# Zhonji_ai8051__Board1_Schematic1__1_P1.net
KiCad netlist of a schematic drawn in Altium Designer
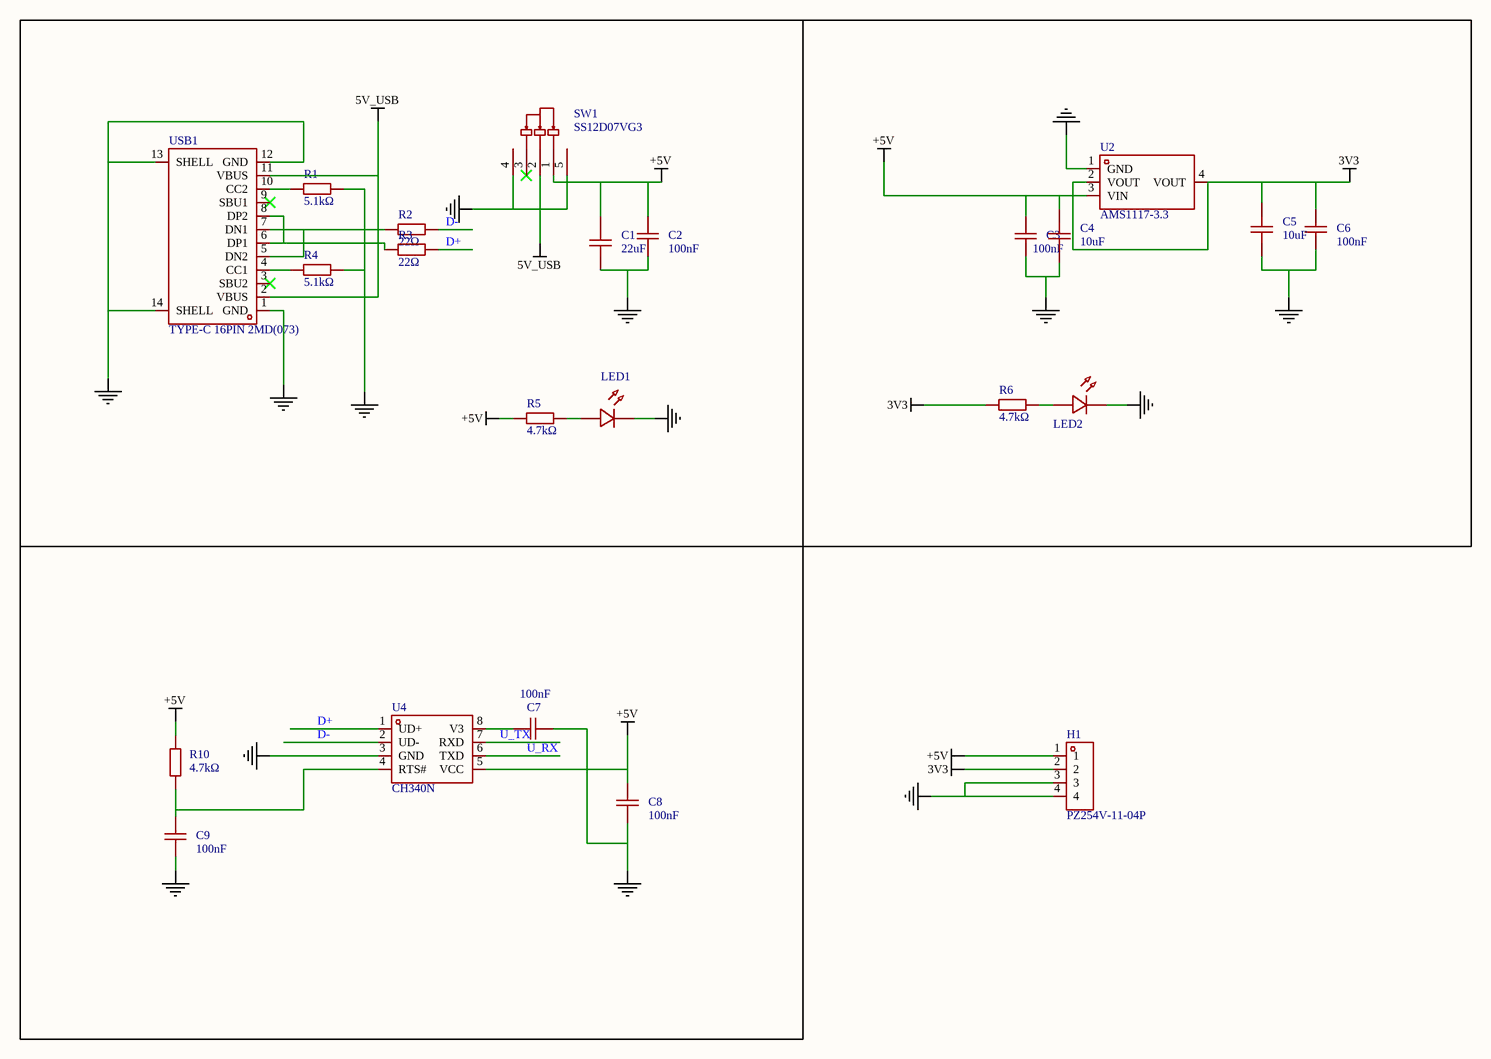
[diagram p0: Zhonji_ai8051__Board1_Schematic1__1_P1.schdoc]

(export (version "E")
  (design (tool "Eeschema 10.0.6"))
  (components
    (comp (ref "C1")
      (value "22uF")
      (footprint "C0603")
      (description "容值:22uF;精度:±20%;额定电压:16V;材质(温度系数):X5R;")
      (fields
        (field (name "MANUFACTURER") "HRE(芯声)")
        (field (name "MANUFACTURER PART") "CGA0603X5R226M160JT")
      )
      (libsource (lib "altium-import") (part "root_1_CGA0603X5R226M160JT_"))
    )
    (comp (ref "C2")
      (value "100nF")
      (footprint "C0603")
      (description "容值:100nF;精度:±10%;额定电压:50V;材质(温度系数):2X1;")
      (fields
        (field (name "MANUFACTURER") "TORCH(火炬)")
        (field (name "MANUFACTURER PART") "CT41G-0603-2X1-50V-0.1μF-K(N)")
      )
      (libsource (lib "altium-import") (part "root_1_CT41G-0603-2X1-50V-0.1μF-K(N)_"))
    )
    (comp (ref "C3")
      (value "100nF")
      (footprint "C0603")
      (description "容值:100nF;精度:±10%;额定电压:50V;材质(温度系数):2X1;")
      (fields
        (field (name "MANUFACTURER") "TORCH(火炬)")
        (field (name "MANUFACTURER PART") "CT41G-0603-2X1-50V-0.1μF-K(N)")
      )
      (libsource (lib "altium-import") (part "root_1_CT41G-0603-2X1-50V-0.1μF-K(N)_"))
    )
    (comp (ref "C4")
      (value "10uF")
      (footprint "C0603")
      (description "容值:10uF;精度:±20%;额定电压:25V;材质(温度系数):X5R;")
      (fields
        (field (name "MANUFACTURER") "SAMSUNG(三星)")
        (field (name "MANUFACTURER PART") "CL10A106MA8NRNC")
      )
      (libsource (lib "altium-import") (part "root_1_CL10A106MA8NRNC_"))
    )
    (comp (ref "C5")
      (value "10uF")
      (footprint "C0603")
      (description "容值:10uF;精度:±20%;额定电压:25V;材质(温度系数):X5R;")
      (fields
        (field (name "MANUFACTURER") "SAMSUNG(三星)")
        (field (name "MANUFACTURER PART") "CL10A106MA8NRNC")
      )
      (libsource (lib "altium-import") (part "root_1_CL10A106MA8NRNC_"))
    )
    (comp (ref "C6")
      (value "100nF")
      (footprint "C0603")
      (description "容值:100nF;精度:±10%;额定电压:50V;材质(温度系数):2X1;")
      (fields
        (field (name "MANUFACTURER") "TORCH(火炬)")
        (field (name "MANUFACTURER PART") "CT41G-0603-2X1-50V-0.1μF-K(N)")
      )
      (libsource (lib "altium-import") (part "root_1_CT41G-0603-2X1-50V-0.1μF-K(N)_"))
    )
    (comp (ref "C7")
      (value "100nF")
      (footprint "C0603")
      (description "容值:100nF;精度:±10%;额定电压:50V;材质(温度系数):2X1;")
      (fields
        (field (name "MANUFACTURER") "TORCH(火炬)")
        (field (name "MANUFACTURER PART") "CT41G-0603-2X1-50V-0.1μF-K(N)")
      )
      (libsource (lib "altium-import") (part "root_2_CT41G-0603-2X1-50V-0.1μF-K(N)_"))
    )
    (comp (ref "C8")
      (value "100nF")
      (footprint "C0603")
      (description "容值:100nF;精度:±10%;额定电压:50V;材质(温度系数):2X1;")
      (fields
        (field (name "MANUFACTURER") "TORCH(火炬)")
        (field (name "MANUFACTURER PART") "CT41G-0603-2X1-50V-0.1μF-K(N)")
      )
      (libsource (lib "altium-import") (part "root_1_CT41G-0603-2X1-50V-0.1μF-K(N)_"))
    )
    (comp (ref "C9")
      (value "100nF")
      (footprint "C0603")
      (description "容值:100nF;精度:±10%;额定电压:50V;材质(温度系数):2X1;")
      (fields
        (field (name "MANUFACTURER") "TORCH(火炬)")
        (field (name "MANUFACTURER PART") "CT41G-0603-2X1-50V-0.1μF-K(N)")
      )
      (libsource (lib "altium-import") (part "root_1_CT41G-0603-2X1-50V-0.1μF-K(N)_"))
    )
    (comp (ref "H1")
      (value "PZ254V-11-04P")
      (footprint "HDR-TH_4P-P2.54-V-M")
      (fields (field (name "MANUFACTURER") "XFCN(兴飞)"))
      (libsource (lib "altium-import") (part "root_0_PZ254V-11-04P_"))
    )
    (comp (ref "LED1")
      (value "LED_0603-G")
      (footprint "LED_0603")
      (libsource (lib "altium-import") (part "root_0_LED_0603-G_"))
    )
    (comp (ref "LED2")
      (value "LED_0603-R")
      (footprint "LED_0603")
      (libsource (lib "altium-import") (part "root_0_LED_0603-R_"))
    )
    (comp (ref "R1")
      (value "5.1kΩ")
      (footprint "R0603")
      (description "电阻类型:厚膜电阻;阻值:5.1kΩ;精度:±1%;功率:100mW;最大工作电压:75V;温度系数:±100ppm/℃;")
      (fields
        (field (name "MANUFACTURER") "UNI-ROYAL(厚声)")
        (field (name "MANUFACTURER PART") "0603WAF5101T5E")
      )
      (libsource (lib "altium-import") (part "root_0_0603WAF5101T5E_"))
    )
    (comp (ref "R2")
      (value "22Ω")
      (footprint "R0603")
      (description "电阻类型:厚膜电阻;阻值:22Ω;精度:±1%;功率:100mW;最大工作电压:75V;温度系数:±100ppm/℃;")
      (fields
        (field (name "MANUFACTURER") "UNI-ROYAL(厚声)")
        (field (name "MANUFACTURER PART") "0603WAF220JT5E")
      )
      (libsource (lib "altium-import") (part "root_0_0603WAF220JT5E_"))
    )
    (comp (ref "R3")
      (value "22Ω")
      (footprint "R0603")
      (description "电阻类型:厚膜电阻;阻值:22Ω;精度:±1%;功率:100mW;最大工作电压:75V;温度系数:±100ppm/℃;")
      (fields
        (field (name "MANUFACTURER") "UNI-ROYAL(厚声)")
        (field (name "MANUFACTURER PART") "0603WAF220JT5E")
      )
      (libsource (lib "altium-import") (part "root_0_0603WAF220JT5E_"))
    )
    (comp (ref "R4")
      (value "5.1kΩ")
      (footprint "R0603")
      (description "电阻类型:厚膜电阻;阻值:5.1kΩ;精度:±1%;功率:100mW;最大工作电压:75V;温度系数:±100ppm/℃;")
      (fields
        (field (name "MANUFACTURER") "UNI-ROYAL(厚声)")
        (field (name "MANUFACTURER PART") "0603WAF5101T5E")
      )
      (libsource (lib "altium-import") (part "root_0_0603WAF5101T5E_"))
    )
    (comp (ref "R5")
      (value "4.7kΩ")
      (footprint "R0603")
      (description "电阻类型:厚膜电阻;阻值:4.7kΩ;精度:±1%;功率:100mW;最大工作电压:75V;温度系数:±100ppm/℃;")
      (fields
        (field (name "MANUFACTURER") "UNI-ROYAL(厚声)")
        (field (name "MANUFACTURER PART") "0603WAF4701T5E")
      )
      (libsource (lib "altium-import") (part "root_0_0603WAF4701T5E_"))
    )
    (comp (ref "R6")
      (value "4.7kΩ")
      (footprint "R0603")
      (description "电阻类型:厚膜电阻;阻值:4.7kΩ;精度:±1%;功率:100mW;最大工作电压:75V;温度系数:±100ppm/℃;")
      (fields
        (field (name "MANUFACTURER") "UNI-ROYAL(厚声)")
        (field (name "MANUFACTURER PART") "0603WAF4701T5E")
      )
      (libsource (lib "altium-import") (part "root_0_0603WAF4701T5E_"))
    )
    (comp (ref "R10")
      (value "4.7kΩ")
      (footprint "R0603")
      (description "电阻类型:厚膜电阻;阻值:4.7kΩ;精度:±1%;功率:100mW;最大工作电压:75V;温度系数:±100ppm/℃;")
      (fields
        (field (name "MANUFACTURER") "UNI-ROYAL(厚声)")
        (field (name "MANUFACTURER PART") "0603WAF4701T5E")
      )
      (libsource (lib "altium-import") (part "root_1_0603WAF4701T5E_"))
    )
    (comp (ref "SW1")
      (value "SS12D07VG3")
      (footprint "SW-TH_SS12D07VG3")
      (description "电路结构:单刀双掷;安装方式:直插;开关颜色:-;额定电流(DC):500mA;额定电压(DC):50V;额定电流(AC):-;额定电压(AC):-;机械寿命:5千次;")
      (fields (field (name "MANUFACTURER") "SHOU HAN(首韩)"))
      (libsource (lib "altium-import") (part "root_2_SS12D07VG3_"))
    )
    (comp (ref "U2")
      (value "AMS1117-3.3")
      (footprint "SOT-223-3_L6.5-W3.4-P2.30-LS7.0-BR")
      (description "输出类型:固定;最大输入电压:-;输出电压:3.3V;最大输出电流:1A;电源纹波抑制比(PSRR):72dB@(120Hz);输出极性:正极;")
      (fields (field (name "MANUFACTURER") "AMS"))
      (libsource (lib "altium-import") (part "root_0_AMS1117-3.3_C6186_"))
    )
    (comp (ref "U4")
      (value "CH340N")
      (footprint "SOP-8_L4.9-W3.9-P1.27-LS6.0-BL")
      (fields (field (name "MANUFACTURER") "WCH(南京沁恒)"))
      (libsource (lib "altium-import") (part "root_0_CH340N_"))
    )
    (comp (ref "USB1")
      (value "TYPE-C 16PIN 2MD(073)")
      (footprint "USB-C-SMD_TYPE-C-6PIN-2MD-073")
      (description "连接器类型:Type-C;标准:USB 3.1;公母:母;安装方式:卧贴;触点数量:16P;端口数量:1;额定电流 - 电源:5A;工作温度范围:-25℃~+85℃;")
      (fields (field (name "MANUFACTURER") "SHOU HAN(首韩)"))
      (libsource (lib "altium-import") (part "root_2_TYPE-C 16PIN 2MD(073)_"))
    )
  )
  (nets
    (net (code "1") (name "+5V") (class "Default")
      (node (ref "C1") (pin "2") (pinfunction "2_2") (pintype "passive"))
      (node (ref "C2") (pin "2") (pinfunction "2_2") (pintype "passive"))
      (node (ref "C3") (pin "2") (pinfunction "2_2") (pintype "passive"))
      (node (ref "C4") (pin "2") (pinfunction "2_2") (pintype "passive"))
      (node (ref "C8") (pin "2") (pinfunction "2_2") (pintype "passive"))
      (node (ref "H1") (pin "1") (pinfunction "1_1") (pintype "passive"))
      (node (ref "R10") (pin "2") (pinfunction "2_2") (pintype "passive"))
      (node (ref "R5") (pin "1") (pinfunction "1_1") (pintype "passive"))
      (node (ref "SW1") (pin "1") (pinfunction "1_1") (pintype "passive"))
      (node (ref "U2") (pin "3") (pinfunction "VIN_3") (pintype "passive"))
      (node (ref "U4") (pin "5") (pinfunction "VCC_5") (pintype "passive"))
    )
    (net (code "2") (name "/D+") (class "Default")
      (node (ref "R3") (pin "2") (pinfunction "2_2") (pintype "passive"))
      (node (ref "U4") (pin "1") (pinfunction "UD+_1") (pintype "passive"))
    )
    (net (code "3") (name "/D-") (class "Default")
      (node (ref "R2") (pin "2") (pinfunction "2_2") (pintype "passive"))
      (node (ref "U4") (pin "2") (pinfunction "UD-_2") (pintype "passive"))
    )
    (net (code "4") (name "/U_RX") (class "Default")
      (node (ref "U4") (pin "6") (pinfunction "TXD_6") (pintype "passive"))
    )
    (net (code "5") (name "/U_TX") (class "Default")
      (node (ref "U4") (pin "7") (pinfunction "RXD_7") (pintype "passive"))
    )
    (net (code "6") (name "3V3") (class "Default")
      (node (ref "C5") (pin "2") (pinfunction "2_2") (pintype "passive"))
      (node (ref "C6") (pin "2") (pinfunction "2_2") (pintype "passive"))
      (node (ref "H1") (pin "2") (pinfunction "2_2") (pintype "passive"))
      (node (ref "R6") (pin "1") (pinfunction "1_1") (pintype "passive"))
      (node (ref "U2") (pin "2") (pinfunction "VOUT_2") (pintype "passive"))
      (node (ref "U2") (pin "4") (pinfunction "VOUT_4") (pintype "passive"))
    )
    (net (code "7") (name "5V_USB") (class "Default")
      (node (ref "SW1") (pin "2") (pinfunction "2_2") (pintype "passive"))
      (node (ref "USB1") (pin "11") (pinfunction "VBUS_11") (pintype "passive"))
      (node (ref "USB1") (pin "2") (pinfunction "VBUS_2") (pintype "passive"))
    )
    (net (code "8") (name "GND") (class "Default")
      (node (ref "C1") (pin "1") (pinfunction "1_1") (pintype "passive"))
      (node (ref "C2") (pin "1") (pinfunction "1_1") (pintype "passive"))
      (node (ref "C3") (pin "1") (pinfunction "1_1") (pintype "passive"))
      (node (ref "C4") (pin "1") (pinfunction "1_1") (pintype "passive"))
      (node (ref "C5") (pin "1") (pinfunction "1_1") (pintype "passive"))
      (node (ref "C6") (pin "1") (pinfunction "1_1") (pintype "passive"))
      (node (ref "C7") (pin "1") (pinfunction "1_1") (pintype "passive"))
      (node (ref "C8") (pin "1") (pinfunction "1_1") (pintype "passive"))
      (node (ref "C9") (pin "1") (pinfunction "1_1") (pintype "passive"))
      (node (ref "H1") (pin "3") (pinfunction "3_3") (pintype "passive"))
      (node (ref "H1") (pin "4") (pinfunction "4_4") (pintype "passive"))
      (node (ref "LED1") (pin "1") (pinfunction "C_1") (pintype "passive"))
      (node (ref "LED2") (pin "1") (pinfunction "C_1") (pintype "passive"))
      (node (ref "R1") (pin "2") (pinfunction "2_2") (pintype "passive"))
      (node (ref "R4") (pin "2") (pinfunction "2_2") (pintype "passive"))
      (node (ref "SW1") (pin "4") (pinfunction "4_4") (pintype "passive"))
      (node (ref "SW1") (pin "5") (pinfunction "5_5") (pintype "passive"))
      (node (ref "U2") (pin "1") (pinfunction "GND_1") (pintype "passive"))
      (node (ref "U4") (pin "3") (pinfunction "GND_3") (pintype "passive"))
      (node (ref "USB1") (pin "1") (pinfunction "GND_1") (pintype "passive"))
      (node (ref "USB1") (pin "12") (pinfunction "GND_12") (pintype "passive"))
      (node (ref "USB1") (pin "13") (pinfunction "SHELL_13") (pintype "passive"))
      (node (ref "USB1") (pin "14") (pinfunction "SHELL_14") (pintype "passive"))
    )
    (net (code "9") (name "Net-(LED1-A)") (class "Default")
      (node (ref "LED1") (pin "2") (pinfunction "A_2") (pintype "passive"))
      (node (ref "R5") (pin "2") (pinfunction "2_2") (pintype "passive"))
    )
    (net (code "10") (name "Net-(LED2-A)") (class "Default")
      (node (ref "LED2") (pin "2") (pinfunction "A_2") (pintype "passive"))
      (node (ref "R6") (pin "2") (pinfunction "2_2") (pintype "passive"))
    )
    (net (code "11") (name "Net-(U4-RTS#)") (class "Default")
      (node (ref "C9") (pin "2") (pinfunction "2_2") (pintype "passive"))
      (node (ref "R10") (pin "1") (pinfunction "1_1") (pintype "passive"))
      (node (ref "U4") (pin "4") (pinfunction "RTS#_4") (pintype "passive"))
    )
    (net (code "12") (name "Net-(U4-V3)") (class "Default")
      (node (ref "C7") (pin "2") (pinfunction "2_2") (pintype "passive"))
      (node (ref "U4") (pin "8") (pinfunction "V3_8") (pintype "passive"))
    )
    (net (code "13") (name "Net-(USB1-CC1)") (class "Default")
      (node (ref "R4") (pin "1") (pinfunction "1_1") (pintype "passive"))
      (node (ref "USB1") (pin "4") (pinfunction "CC1_4") (pintype "passive"))
    )
    (net (code "14") (name "Net-(USB1-CC2)") (class "Default")
      (node (ref "R1") (pin "1") (pinfunction "1_1") (pintype "passive"))
      (node (ref "USB1") (pin "10") (pinfunction "CC2_10") (pintype "passive"))
    )
    (net (code "15") (name "Net-(USB1-DN1)") (class "Default")
      (node (ref "R2") (pin "1") (pinfunction "1_1") (pintype "passive"))
      (node (ref "USB1") (pin "5") (pinfunction "DN2_5") (pintype "passive"))
      (node (ref "USB1") (pin "7") (pinfunction "DN1_7") (pintype "passive"))
    )
    (net (code "16") (name "Net-(USB1-DP1)") (class "Default")
      (node (ref "R3") (pin "1") (pinfunction "1_1") (pintype "passive"))
      (node (ref "USB1") (pin "6") (pinfunction "DP1_6") (pintype "passive"))
      (node (ref "USB1") (pin "8") (pinfunction "DP2_8") (pintype "passive"))
    )
    (net (code "17") (name "unconnected-(SW1-Pad3)") (class "Default")
      (node (ref "SW1") (pin "3") (pinfunction "3_3") (pintype "passive+no_connect"))
    )
    (net (code "18") (name "unconnected-(USB1-SBU1-Pad9)") (class "Default")
      (node (ref "USB1") (pin "9") (pinfunction "SBU1_9") (pintype "passive+no_connect"))
    )
    (net (code "19") (name "unconnected-(USB1-SBU2-Pad3)") (class "Default")
      (node (ref "USB1") (pin "3") (pinfunction "SBU2_3") (pintype "passive+no_connect"))
    )
  )
)
